# analog-devices.net
KiCad netlist of a schematic drawn in EAGLE
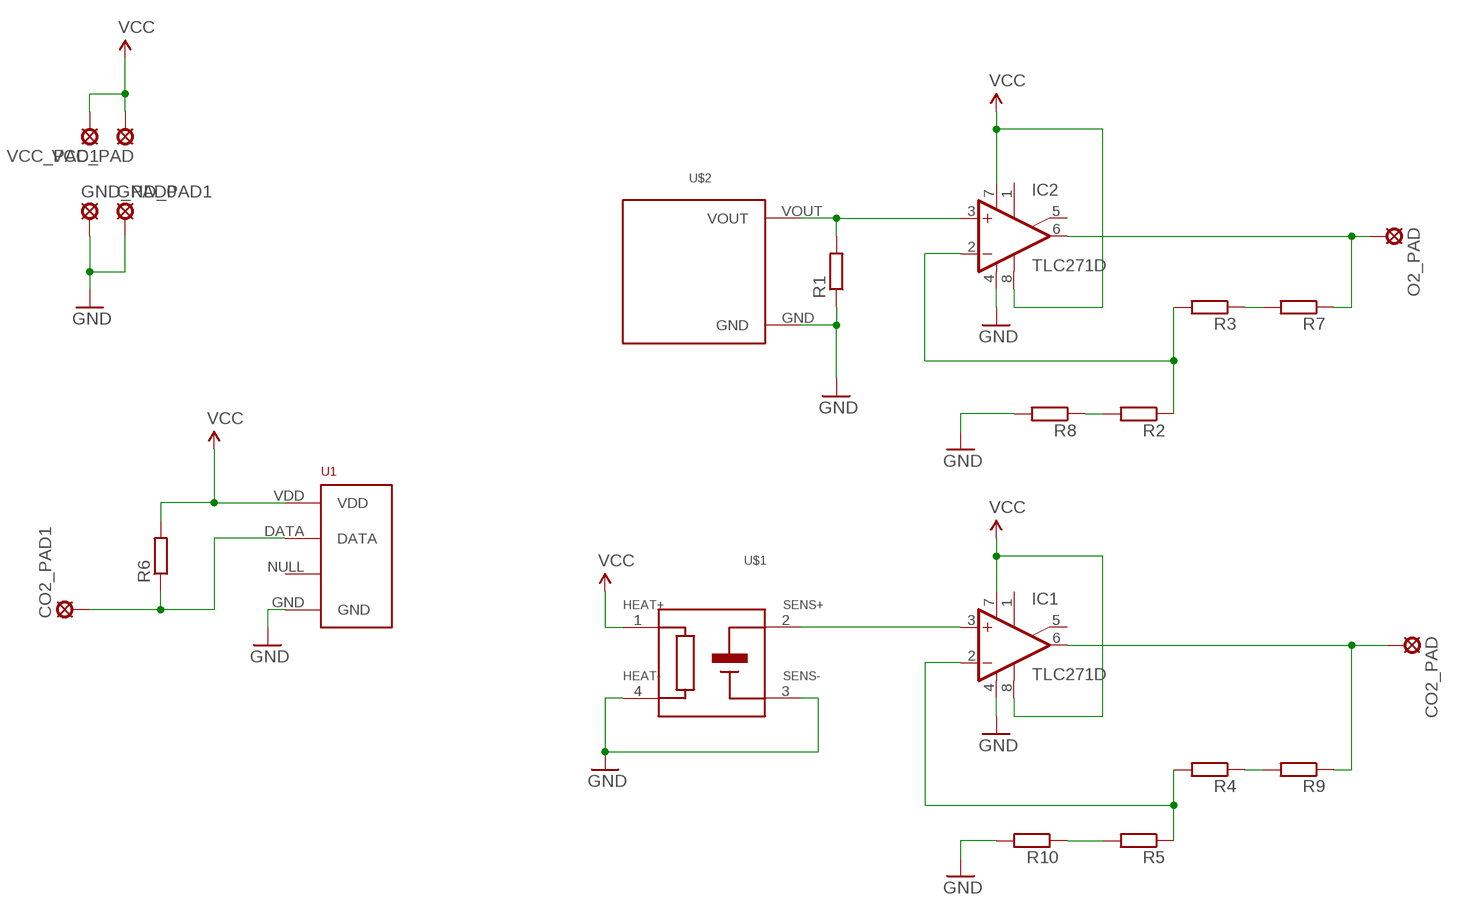
[diagram p0: schematic, sheet 1]

(export (version "E")
  (design (tool "Eeschema 10.0.6"))
  (components
    (comp (ref "CO2_PAD")
      (value "LSP10")
      (footprint "eagle-import:LSP10")
      (libsource (lib "eagle-import") (part "LSP10"))
    )
    (comp (ref "CO2_PAD1")
      (value "LSP10")
      (footprint "eagle-import:LSP10")
      (libsource (lib "eagle-import") (part "LSP10"))
    )
    (comp (ref "GND_PAD0")
      (value "LSP10")
      (footprint "eagle-import:LSP10")
      (libsource (lib "eagle-import") (part "LSP10"))
    )
    (comp (ref "GND_PAD1")
      (value "LSP10")
      (footprint "eagle-import:LSP10")
      (libsource (lib "eagle-import") (part "LSP10"))
    )
    (comp (ref "IC1")
      (value "TLC271D")
      (footprint "eagle-import:SO08")
      (libsource (lib "eagle-import") (part "TLC271D"))
    )
    (comp (ref "IC2")
      (value "TLC271D")
      (footprint "eagle-import:SO08")
      (libsource (lib "eagle-import") (part "TLC271D"))
    )
    (comp (ref "O2_PAD")
      (value "LSP10")
      (footprint "eagle-import:LSP10")
      (libsource (lib "eagle-import") (part "LSP10"))
    )
    (comp (ref "R1")
      (value "R-EU_R0805")
      (footprint "eagle-import:R0805")
      (libsource (lib "eagle-import") (part "R-EU_R0805"))
    )
    (comp (ref "R2")
      (value "R-EU_R0805")
      (footprint "eagle-import:R0805")
      (libsource (lib "eagle-import") (part "R-EU_R0805"))
    )
    (comp (ref "R3")
      (value "R-EU_R0805")
      (footprint "eagle-import:R0805")
      (libsource (lib "eagle-import") (part "R-EU_R0805"))
    )
    (comp (ref "R4")
      (value "R-EU_R0805")
      (footprint "eagle-import:R0805")
      (libsource (lib "eagle-import") (part "R-EU_R0805"))
    )
    (comp (ref "R5")
      (value "R-EU_R0805")
      (footprint "eagle-import:R0805")
      (libsource (lib "eagle-import") (part "R-EU_R0805"))
    )
    (comp (ref "R6")
      (value "R-EU_R0805")
      (footprint "eagle-import:R0805")
      (libsource (lib "eagle-import") (part "R-EU_R0805"))
    )
    (comp (ref "R7")
      (value "R-EU_R0805")
      (footprint "eagle-import:R0805")
      (libsource (lib "eagle-import") (part "R-EU_R0805"))
    )
    (comp (ref "R8")
      (value "R-EU_R0805")
      (footprint "eagle-import:R0805")
      (libsource (lib "eagle-import") (part "R-EU_R0805"))
    )
    (comp (ref "R9")
      (value "R-EU_R0805")
      (footprint "eagle-import:R0805")
      (libsource (lib "eagle-import") (part "R-EU_R0805"))
    )
    (comp (ref "R10")
      (value "R-EU_R0805")
      (footprint "eagle-import:R0805")
      (libsource (lib "eagle-import") (part "R-EU_R0805"))
    )
    (comp (ref "U$1")
      (value "TGS4161")
      (footprint "eagle-import:TGS4161")
      (libsource (lib "eagle-import") (part "TGS4161"))
    )
    (comp (ref "U$2")
      (value "O2-A2")
      (footprint "eagle-import:O2-A2")
      (libsource (lib "eagle-import") (part "O2-A2"))
    )
    (comp (ref "U1")
      (value "RHT03_DHT-22_AM2302RA")
      (footprint "eagle-import:RHT03_DHT-22_RA")
      (libsource (lib "eagle-import") (part "RHT03_DHT-22_AM2302RA"))
    )
    (comp (ref "VCC_PAD")
      (value "LSP10")
      (footprint "eagle-import:LSP10")
      (libsource (lib "eagle-import") (part "LSP10"))
    )
    (comp (ref "VCC_PAD1")
      (value "LSP10")
      (footprint "eagle-import:LSP10")
      (libsource (lib "eagle-import") (part "LSP10"))
    )
  )
  (nets
    (net (code "1") (name "GND") (class "Default")
      (node (ref "GND_PAD0") (pin "MP") (pinfunction "MP_MP") (pintype "passive"))
      (node (ref "GND_PAD1") (pin "MP") (pinfunction "MP_MP") (pintype "passive"))
      (node (ref "IC1") (pin "4") (pinfunction "V-_4") (pintype "power_in"))
      (node (ref "IC2") (pin "4") (pinfunction "V-_4") (pintype "power_in"))
      (node (ref "R1") (pin "1") (pinfunction "1_1") (pintype "passive"))
      (node (ref "R10") (pin "2") (pinfunction "2_2") (pintype "passive"))
      (node (ref "R8") (pin "2") (pinfunction "2_2") (pintype "passive"))
      (node (ref "U$1") (pin "3") (pinfunction "SENS-_3") (pintype "passive"))
      (node (ref "U$1") (pin "4") (pinfunction "HEAT-_4") (pintype "power_in"))
      (node (ref "U$2") (pin "GND") (pinfunction "GND_GND") (pintype "bidirectional"))
      (node (ref "U1") (pin "GND") (pinfunction "GND_GND") (pintype "power_in"))
    )
    (net (code "2") (name "Net-(CO2_PAD1-PadMP)") (class "Default")
      (node (ref "CO2_PAD1") (pin "MP") (pinfunction "MP_MP") (pintype "passive"))
      (node (ref "R6") (pin "1") (pinfunction "1_1") (pintype "passive"))
      (node (ref "U1") (pin "DATA") (pinfunction "DATA_DATA") (pintype "bidirectional"))
    )
    (net (code "3") (name "Net-(IC1-+IN)") (class "Default")
      (node (ref "IC1") (pin "3") (pinfunction "+IN_3") (pintype "input"))
      (node (ref "U$1") (pin "2") (pinfunction "SENS+_2") (pintype "passive"))
    )
    (net (code "4") (name "Net-(IC1--IN)") (class "Default")
      (node (ref "IC1") (pin "2") (pinfunction "-IN_2") (pintype "input"))
      (node (ref "R4") (pin "2") (pinfunction "2_2") (pintype "passive"))
      (node (ref "R5") (pin "1") (pinfunction "1_1") (pintype "passive"))
    )
    (net (code "5") (name "Net-(IC1-OUT)") (class "Default")
      (node (ref "CO2_PAD") (pin "MP") (pinfunction "MP_MP") (pintype "passive"))
      (node (ref "IC1") (pin "6") (pinfunction "OUT_6") (pintype "output"))
      (node (ref "R9") (pin "1") (pinfunction "1_1") (pintype "passive"))
    )
    (net (code "6") (name "Net-(IC2-+IN)") (class "Default")
      (node (ref "IC2") (pin "3") (pinfunction "+IN_3") (pintype "input"))
      (node (ref "R1") (pin "2") (pinfunction "2_2") (pintype "passive"))
      (node (ref "U$2") (pin "VOUT") (pinfunction "VOUT_VOUT") (pintype "bidirectional"))
    )
    (net (code "7") (name "Net-(IC2--IN)") (class "Default")
      (node (ref "IC2") (pin "2") (pinfunction "-IN_2") (pintype "input"))
      (node (ref "R2") (pin "1") (pinfunction "1_1") (pintype "passive"))
      (node (ref "R3") (pin "2") (pinfunction "2_2") (pintype "passive"))
    )
    (net (code "8") (name "Net-(IC2-OUT)") (class "Default")
      (node (ref "IC2") (pin "6") (pinfunction "OUT_6") (pintype "output"))
      (node (ref "O2_PAD") (pin "MP") (pinfunction "MP_MP") (pintype "passive"))
      (node (ref "R7") (pin "1") (pinfunction "1_1") (pintype "passive"))
    )
    (net (code "9") (name "Net-(R2-Pad2)") (class "Default")
      (node (ref "R2") (pin "2") (pinfunction "2_2") (pintype "passive"))
      (node (ref "R8") (pin "1") (pinfunction "1_1") (pintype "passive"))
    )
    (net (code "10") (name "Net-(R3-Pad1)") (class "Default")
      (node (ref "R3") (pin "1") (pinfunction "1_1") (pintype "passive"))
      (node (ref "R7") (pin "2") (pinfunction "2_2") (pintype "passive"))
    )
    (net (code "11") (name "Net-(R4-Pad1)") (class "Default")
      (node (ref "R4") (pin "1") (pinfunction "1_1") (pintype "passive"))
      (node (ref "R9") (pin "2") (pinfunction "2_2") (pintype "passive"))
    )
    (net (code "12") (name "Net-(R10-Pad1)") (class "Default")
      (node (ref "R10") (pin "1") (pinfunction "1_1") (pintype "passive"))
      (node (ref "R5") (pin "2") (pinfunction "2_2") (pintype "passive"))
    )
    (net (code "13") (name "VCC") (class "Default")
      (node (ref "IC1") (pin "7") (pinfunction "V+_7") (pintype "power_in"))
      (node (ref "IC1") (pin "8") (pinfunction "OPT_8") (pintype "passive"))
      (node (ref "IC2") (pin "7") (pinfunction "V+_7") (pintype "power_in"))
      (node (ref "IC2") (pin "8") (pinfunction "OPT_8") (pintype "passive"))
      (node (ref "R6") (pin "2") (pinfunction "2_2") (pintype "passive"))
      (node (ref "U$1") (pin "1") (pinfunction "HEAT+_1") (pintype "power_in"))
      (node (ref "U1") (pin "VDD") (pinfunction "VDD_VDD") (pintype "power_in"))
      (node (ref "VCC_PAD") (pin "MP") (pinfunction "MP_MP") (pintype "passive"))
      (node (ref "VCC_PAD1") (pin "MP") (pinfunction "MP_MP") (pintype "passive"))
    )
    (net (code "14") (name "unconnected-(IC1-ON1-Pad1)") (class "Default")
      (node (ref "IC1") (pin "1") (pinfunction "ON1_1") (pintype "passive"))
    )
    (net (code "15") (name "unconnected-(IC1-ON2-Pad5)") (class "Default")
      (node (ref "IC1") (pin "5") (pinfunction "ON2_5") (pintype "passive"))
    )
    (net (code "16") (name "unconnected-(IC2-ON1-Pad1)") (class "Default")
      (node (ref "IC2") (pin "1") (pinfunction "ON1_1") (pintype "passive"))
    )
    (net (code "17") (name "unconnected-(IC2-ON2-Pad5)") (class "Default")
      (node (ref "IC2") (pin "5") (pinfunction "ON2_5") (pintype "passive"))
    )
    (net (code "18") (name "unconnected-(U1-PadNULL)") (class "Default")
      (node (ref "U1") (pin "NULL") (pinfunction "NULL_NULL") (pintype "no_connect"))
    )
  )
)
